# CAN_bus_powered.net
KiCad netlist of a schematic drawn in Altium Designer
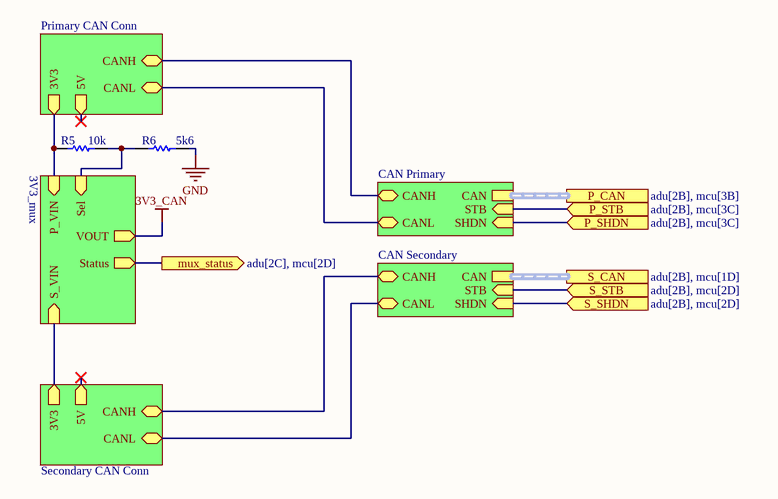
[diagram p0: CAN_bus_powered.SchDoc]

(export (version "E")
  (design (tool "Eeschema 10.0.6"))
  (components
    (comp (ref "R5")
      (value "10k")
      (footprint "RES-0603")
      (description "Resistor")
      (libsource (lib "drfc_schlib") (part "Resistor"))
    )
    (comp (ref "R6")
      (value "5k6")
      (footprint "RES-0603")
      (description "Resistor")
      (libsource (lib "drfc_schlib") (part "Resistor"))
    )
  )
  (nets
    (net (code "4") (name "/3V3_1") (class "Default")
      (node (ref "R5") (pin "2") (pinfunction "2_2") (pintype "passive"))
    )
    (net (code "17") (name "/Sel") (class "Default")
      (node (ref "R5") (pin "1") (pinfunction "1_1") (pintype "passive"))
      (node (ref "R6") (pin "2") (pinfunction "2_2") (pintype "passive"))
    )
    (net (code "20") (name "GND") (class "Default")
      (node (ref "R6") (pin "1") (pinfunction "1_1") (pintype "passive"))
    )
  )
)
